# mult-mixer.net
KiCad netlist of a schematic drawn in EAGLE
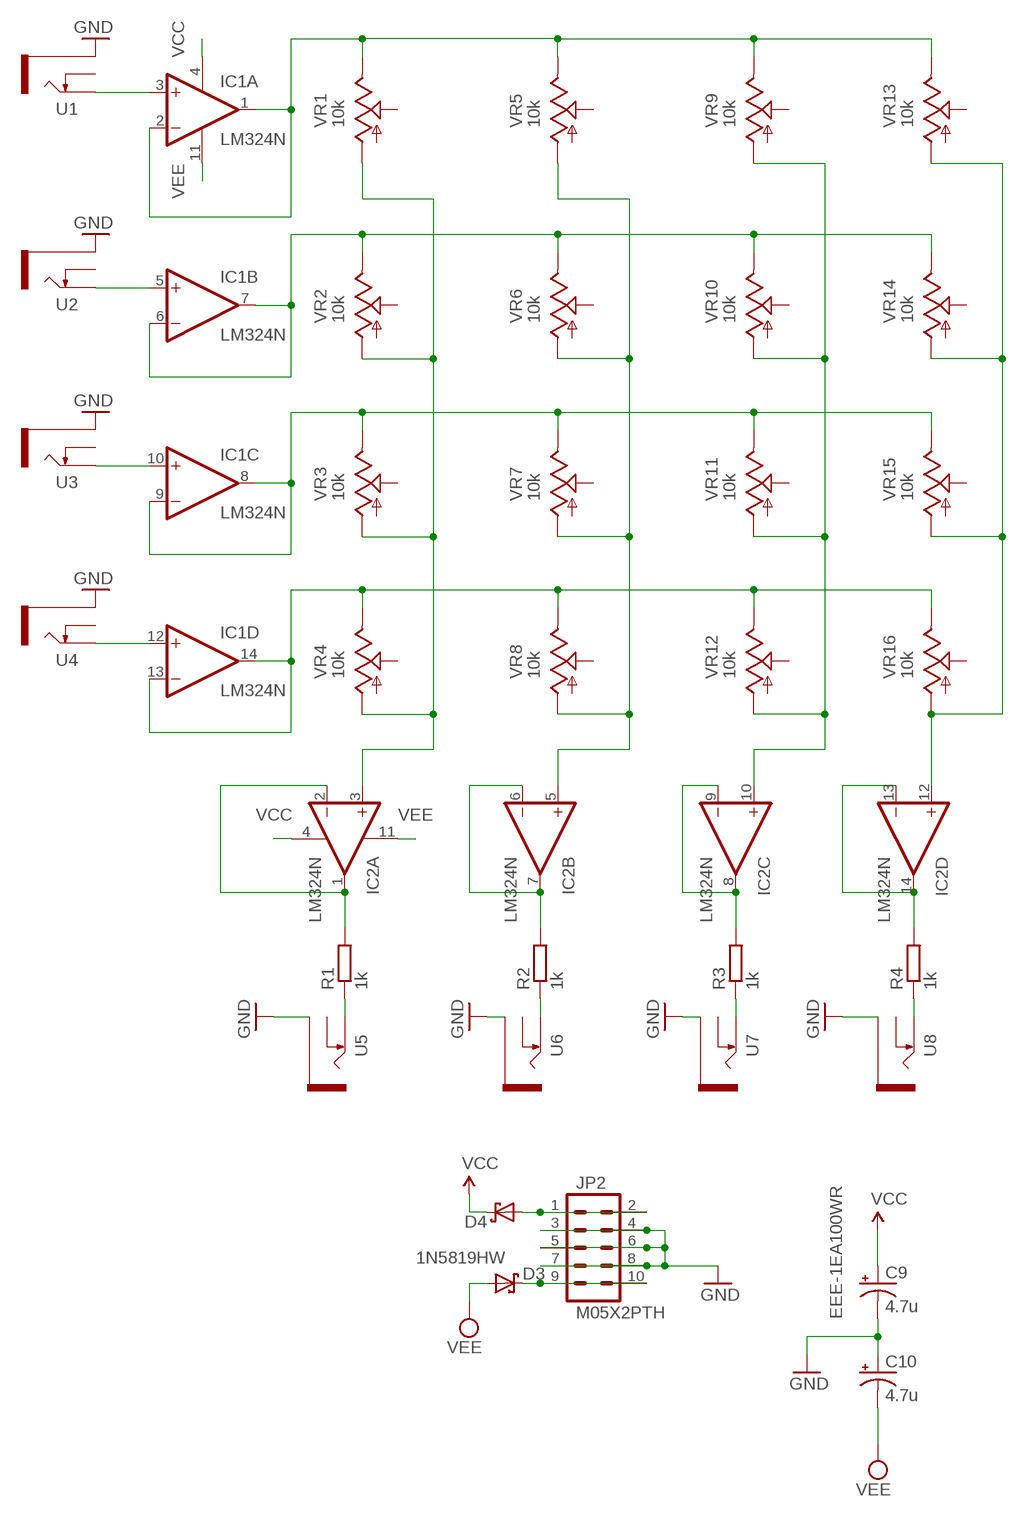
[diagram p0: schematic, sheet 1]

(export (version "E")
  (design (tool "Eeschema 10.0.6"))
  (components
    (comp (ref "C9")
      (value "4.7u")
      (footprint "eagle-import:PANASONIC_A")
      (libsource (lib "eagle-import") (part "CPOL-USA"))
    )
    (comp (ref "C10")
      (value "4.7u")
      (footprint "eagle-import:PANASONIC_A")
      (libsource (lib "eagle-import") (part "CPOL-USA"))
    )
    (comp (ref "D3")
      (value "1N5819HW")
      (footprint "eagle-import:DO41-7.6")
      (libsource (lib "eagle-import") (part "1N5819-B"))
    )
    (comp (ref "D4")
      (value "1N5819HW")
      (footprint "eagle-import:DO41-7.6")
      (libsource (lib "eagle-import") (part "1N5819-B"))
    )
    (comp (ref "IC1")
      (value "LM324N")
      (footprint "eagle-import:DIL14")
      (libsource (lib "eagle-import") (part "LM324N"))
    )
    (comp (ref "IC2")
      (value "LM324N")
      (footprint "eagle-import:DIL14")
      (libsource (lib "eagle-import") (part "LM324N"))
    )
    (comp (ref "JP2")
      (value "M05X2PTH")
      (footprint "eagle-import:AVR_ICSP")
      (libsource (lib "eagle-import") (part "M05X2PTH"))
    )
    (comp (ref "R1")
      (value "1k")
      (footprint "eagle-import:10MM_RESISTOR")
      (libsource (lib "eagle-import") (part "RESISTOR10MM_RESISTOR"))
    )
    (comp (ref "R2")
      (value "1k")
      (footprint "eagle-import:10MM_RESISTOR")
      (libsource (lib "eagle-import") (part "RESISTOR10MM_RESISTOR"))
    )
    (comp (ref "R3")
      (value "1k")
      (footprint "eagle-import:10MM_RESISTOR")
      (libsource (lib "eagle-import") (part "RESISTOR10MM_RESISTOR"))
    )
    (comp (ref "R4")
      (value "1k")
      (footprint "eagle-import:10MM_RESISTOR")
      (libsource (lib "eagle-import") (part "RESISTOR10MM_RESISTOR"))
    )
    (comp (ref "U1")
      (value "THONKICONNNEW")
      (footprint "eagle-import:WQP-PJ301M-12_JACK")
      (libsource (lib "eagle-import") (part "THONKICONNNEW"))
    )
    (comp (ref "U2")
      (value "THONKICONNNEW")
      (footprint "eagle-import:WQP-PJ301M-12_JACK")
      (libsource (lib "eagle-import") (part "THONKICONNNEW"))
    )
    (comp (ref "U3")
      (value "THONKICONNNEW")
      (footprint "eagle-import:WQP-PJ301M-12_JACK")
      (libsource (lib "eagle-import") (part "THONKICONNNEW"))
    )
    (comp (ref "U4")
      (value "THONKICONNNEW")
      (footprint "eagle-import:WQP-PJ301M-12_JACK")
      (libsource (lib "eagle-import") (part "THONKICONNNEW"))
    )
    (comp (ref "U5")
      (value "THONKICONNNEW")
      (footprint "eagle-import:WQP-PJ301M-12_JACK")
      (libsource (lib "eagle-import") (part "THONKICONNNEW"))
    )
    (comp (ref "U6")
      (value "THONKICONNNEW")
      (footprint "eagle-import:WQP-PJ301M-12_JACK")
      (libsource (lib "eagle-import") (part "THONKICONNNEW"))
    )
    (comp (ref "U7")
      (value "THONKICONNNEW")
      (footprint "eagle-import:WQP-PJ301M-12_JACK")
      (libsource (lib "eagle-import") (part "THONKICONNNEW"))
    )
    (comp (ref "U8")
      (value "THONKICONNNEW")
      (footprint "eagle-import:WQP-PJ301M-12_JACK")
      (libsource (lib "eagle-import") (part "THONKICONNNEW"))
    )
    (comp (ref "VR1")
      (value "10k")
      (footprint "eagle-import:9MM_SNAP-IN_POT")
      (libsource (lib "eagle-import") (part "9MM_SNAP-IN_POT_"))
    )
    (comp (ref "VR2")
      (value "10k")
      (footprint "eagle-import:9MM_SNAP-IN_POT")
      (libsource (lib "eagle-import") (part "9MM_SNAP-IN_POT_"))
    )
    (comp (ref "VR3")
      (value "10k")
      (footprint "eagle-import:9MM_SNAP-IN_POT")
      (libsource (lib "eagle-import") (part "9MM_SNAP-IN_POT_"))
    )
    (comp (ref "VR4")
      (value "10k")
      (footprint "eagle-import:9MM_SNAP-IN_POT")
      (libsource (lib "eagle-import") (part "9MM_SNAP-IN_POT_"))
    )
    (comp (ref "VR5")
      (value "10k")
      (footprint "eagle-import:9MM_SNAP-IN_POT")
      (libsource (lib "eagle-import") (part "9MM_SNAP-IN_POT_"))
    )
    (comp (ref "VR6")
      (value "10k")
      (footprint "eagle-import:9MM_SNAP-IN_POT")
      (libsource (lib "eagle-import") (part "9MM_SNAP-IN_POT_"))
    )
    (comp (ref "VR7")
      (value "10k")
      (footprint "eagle-import:9MM_SNAP-IN_POT")
      (libsource (lib "eagle-import") (part "9MM_SNAP-IN_POT_"))
    )
    (comp (ref "VR8")
      (value "10k")
      (footprint "eagle-import:9MM_SNAP-IN_POT")
      (libsource (lib "eagle-import") (part "9MM_SNAP-IN_POT_"))
    )
    (comp (ref "VR9")
      (value "10k")
      (footprint "eagle-import:9MM_SNAP-IN_POT")
      (libsource (lib "eagle-import") (part "9MM_SNAP-IN_POT_"))
    )
    (comp (ref "VR10")
      (value "10k")
      (footprint "eagle-import:9MM_SNAP-IN_POT")
      (libsource (lib "eagle-import") (part "9MM_SNAP-IN_POT_"))
    )
    (comp (ref "VR11")
      (value "10k")
      (footprint "eagle-import:9MM_SNAP-IN_POT")
      (libsource (lib "eagle-import") (part "9MM_SNAP-IN_POT_"))
    )
    (comp (ref "VR12")
      (value "10k")
      (footprint "eagle-import:9MM_SNAP-IN_POT")
      (libsource (lib "eagle-import") (part "9MM_SNAP-IN_POT_"))
    )
    (comp (ref "VR13")
      (value "10k")
      (footprint "eagle-import:9MM_SNAP-IN_POT")
      (libsource (lib "eagle-import") (part "9MM_SNAP-IN_POT_"))
    )
    (comp (ref "VR14")
      (value "10k")
      (footprint "eagle-import:9MM_SNAP-IN_POT")
      (libsource (lib "eagle-import") (part "9MM_SNAP-IN_POT_"))
    )
    (comp (ref "VR15")
      (value "10k")
      (footprint "eagle-import:9MM_SNAP-IN_POT")
      (libsource (lib "eagle-import") (part "9MM_SNAP-IN_POT_"))
    )
    (comp (ref "VR16")
      (value "10k")
      (footprint "eagle-import:9MM_SNAP-IN_POT")
      (libsource (lib "eagle-import") (part "9MM_SNAP-IN_POT_"))
    )
  )
  (nets
    (net (code "1") (name "GND") (class "Default")
      (node (ref "C10") (pin "+") (pinfunction "+_+") (pintype "passive"))
      (node (ref "C9") (pin "-") (pinfunction "-_-") (pintype "passive"))
      (node (ref "JP2") (pin "3") (pinfunction "3_3") (pintype "passive"))
      (node (ref "JP2") (pin "4") (pinfunction "4_4") (pintype "passive"))
      (node (ref "JP2") (pin "5") (pinfunction "5_5") (pintype "passive"))
      (node (ref "JP2") (pin "6") (pinfunction "6_6") (pintype "passive"))
      (node (ref "JP2") (pin "7") (pinfunction "7_7") (pintype "passive"))
      (node (ref "JP2") (pin "8") (pinfunction "8_8") (pintype "passive"))
      (node (ref "U1") (pin "P$3_SLEEVE") (pinfunction "SLEEVE_P$3_SLEEVE") (pintype "passive"))
      (node (ref "U2") (pin "P$3_SLEEVE") (pinfunction "SLEEVE_P$3_SLEEVE") (pintype "passive"))
      (node (ref "U3") (pin "P$3_SLEEVE") (pinfunction "SLEEVE_P$3_SLEEVE") (pintype "passive"))
      (node (ref "U4") (pin "P$3_SLEEVE") (pinfunction "SLEEVE_P$3_SLEEVE") (pintype "passive"))
      (node (ref "U5") (pin "P$3_SLEEVE") (pinfunction "SLEEVE_P$3_SLEEVE") (pintype "passive"))
      (node (ref "U6") (pin "P$3_SLEEVE") (pinfunction "SLEEVE_P$3_SLEEVE") (pintype "passive"))
      (node (ref "U7") (pin "P$3_SLEEVE") (pinfunction "SLEEVE_P$3_SLEEVE") (pintype "passive"))
      (node (ref "U8") (pin "P$3_SLEEVE") (pinfunction "SLEEVE_P$3_SLEEVE") (pintype "passive"))
    )
    (net (code "2") (name "Net-(D3-PadC)") (class "Default")
      (node (ref "D3") (pin "C") (pinfunction "C_C") (pintype "passive"))
      (node (ref "JP2") (pin "10") (pinfunction "10_10") (pintype "passive"))
      (node (ref "JP2") (pin "9") (pinfunction "9_9") (pintype "passive"))
    )
    (net (code "3") (name "Net-(D4-PadA)") (class "Default")
      (node (ref "D4") (pin "A") (pinfunction "A_A") (pintype "passive"))
      (node (ref "JP2") (pin "1") (pinfunction "1_1") (pintype "passive"))
      (node (ref "JP2") (pin "2") (pinfunction "2_2") (pintype "passive"))
    )
    (net (code "4") (name "Net-(IC1A-+IN)") (class "Default")
      (node (ref "IC1") (pin "3") (pinfunction "+IN_3") (pintype "input"))
      (node (ref "U1") (pin "P$1_TIP") (pinfunction "TIP_P$1_TIP") (pintype "passive"))
    )
    (net (code "5") (name "Net-(IC1A--IN)") (class "Default")
      (node (ref "IC1") (pin "1") (pinfunction "OUT_1") (pintype "output"))
      (node (ref "IC1") (pin "2") (pinfunction "-IN_2") (pintype "input"))
      (node (ref "VR1") (pin "3") (pinfunction "E_3") (pintype "passive"))
      (node (ref "VR13") (pin "3") (pinfunction "E_3") (pintype "passive"))
      (node (ref "VR5") (pin "3") (pinfunction "E_3") (pintype "passive"))
      (node (ref "VR9") (pin "3") (pinfunction "E_3") (pintype "passive"))
    )
    (net (code "6") (name "Net-(IC1B-+IN)") (class "Default")
      (node (ref "IC1") (pin "5") (pinfunction "+IN_5") (pintype "input"))
      (node (ref "U2") (pin "P$1_TIP") (pinfunction "TIP_P$1_TIP") (pintype "passive"))
    )
    (net (code "7") (name "Net-(IC1B--IN)") (class "Default")
      (node (ref "IC1") (pin "6") (pinfunction "-IN_6") (pintype "input"))
      (node (ref "IC1") (pin "7") (pinfunction "OUT_7") (pintype "output"))
      (node (ref "VR10") (pin "3") (pinfunction "E_3") (pintype "passive"))
      (node (ref "VR14") (pin "3") (pinfunction "E_3") (pintype "passive"))
      (node (ref "VR2") (pin "3") (pinfunction "E_3") (pintype "passive"))
      (node (ref "VR6") (pin "3") (pinfunction "E_3") (pintype "passive"))
    )
    (net (code "8") (name "Net-(IC1C-+IN)") (class "Default")
      (node (ref "IC1") (pin "10") (pinfunction "+IN_10") (pintype "input"))
      (node (ref "U3") (pin "P$1_TIP") (pinfunction "TIP_P$1_TIP") (pintype "passive"))
    )
    (net (code "9") (name "Net-(IC1C--IN)") (class "Default")
      (node (ref "IC1") (pin "8") (pinfunction "OUT_8") (pintype "output"))
      (node (ref "IC1") (pin "9") (pinfunction "-IN_9") (pintype "input"))
      (node (ref "VR11") (pin "3") (pinfunction "E_3") (pintype "passive"))
      (node (ref "VR15") (pin "3") (pinfunction "E_3") (pintype "passive"))
      (node (ref "VR3") (pin "3") (pinfunction "E_3") (pintype "passive"))
      (node (ref "VR7") (pin "3") (pinfunction "E_3") (pintype "passive"))
    )
    (net (code "10") (name "Net-(IC1D-+IN)") (class "Default")
      (node (ref "IC1") (pin "12") (pinfunction "+IN_12") (pintype "input"))
      (node (ref "U4") (pin "P$1_TIP") (pinfunction "TIP_P$1_TIP") (pintype "passive"))
    )
    (net (code "11") (name "Net-(IC1D--IN)") (class "Default")
      (node (ref "IC1") (pin "13") (pinfunction "-IN_13") (pintype "input"))
      (node (ref "IC1") (pin "14") (pinfunction "OUT_14") (pintype "output"))
      (node (ref "VR12") (pin "3") (pinfunction "E_3") (pintype "passive"))
      (node (ref "VR16") (pin "3") (pinfunction "E_3") (pintype "passive"))
      (node (ref "VR4") (pin "3") (pinfunction "E_3") (pintype "passive"))
      (node (ref "VR8") (pin "3") (pinfunction "E_3") (pintype "passive"))
    )
    (net (code "12") (name "Net-(IC2A-+IN)") (class "Default")
      (node (ref "IC2") (pin "3") (pinfunction "+IN_3") (pintype "input"))
      (node (ref "VR1") (pin "1") (pinfunction "A_1") (pintype "passive"))
      (node (ref "VR2") (pin "1") (pinfunction "A_1") (pintype "passive"))
      (node (ref "VR3") (pin "1") (pinfunction "A_1") (pintype "passive"))
      (node (ref "VR4") (pin "1") (pinfunction "A_1") (pintype "passive"))
    )
    (net (code "13") (name "Net-(IC2A--IN)") (class "Default")
      (node (ref "IC2") (pin "1") (pinfunction "OUT_1") (pintype "output"))
      (node (ref "IC2") (pin "2") (pinfunction "-IN_2") (pintype "input"))
      (node (ref "R1") (pin "2") (pinfunction "2_2") (pintype "passive"))
    )
    (net (code "14") (name "Net-(IC2B-+IN)") (class "Default")
      (node (ref "IC2") (pin "5") (pinfunction "+IN_5") (pintype "input"))
      (node (ref "VR5") (pin "1") (pinfunction "A_1") (pintype "passive"))
      (node (ref "VR6") (pin "1") (pinfunction "A_1") (pintype "passive"))
      (node (ref "VR7") (pin "1") (pinfunction "A_1") (pintype "passive"))
      (node (ref "VR8") (pin "1") (pinfunction "A_1") (pintype "passive"))
    )
    (net (code "15") (name "Net-(IC2B--IN)") (class "Default")
      (node (ref "IC2") (pin "6") (pinfunction "-IN_6") (pintype "input"))
      (node (ref "IC2") (pin "7") (pinfunction "OUT_7") (pintype "output"))
      (node (ref "R2") (pin "2") (pinfunction "2_2") (pintype "passive"))
    )
    (net (code "16") (name "Net-(IC2C-+IN)") (class "Default")
      (node (ref "IC2") (pin "10") (pinfunction "+IN_10") (pintype "input"))
      (node (ref "VR10") (pin "1") (pinfunction "A_1") (pintype "passive"))
      (node (ref "VR11") (pin "1") (pinfunction "A_1") (pintype "passive"))
      (node (ref "VR12") (pin "1") (pinfunction "A_1") (pintype "passive"))
      (node (ref "VR9") (pin "1") (pinfunction "A_1") (pintype "passive"))
    )
    (net (code "17") (name "Net-(IC2C--IN)") (class "Default")
      (node (ref "IC2") (pin "8") (pinfunction "OUT_8") (pintype "output"))
      (node (ref "IC2") (pin "9") (pinfunction "-IN_9") (pintype "input"))
      (node (ref "R3") (pin "2") (pinfunction "2_2") (pintype "passive"))
    )
    (net (code "18") (name "Net-(IC2D-+IN)") (class "Default")
      (node (ref "IC2") (pin "12") (pinfunction "+IN_12") (pintype "input"))
      (node (ref "VR13") (pin "1") (pinfunction "A_1") (pintype "passive"))
      (node (ref "VR14") (pin "1") (pinfunction "A_1") (pintype "passive"))
      (node (ref "VR15") (pin "1") (pinfunction "A_1") (pintype "passive"))
      (node (ref "VR16") (pin "1") (pinfunction "A_1") (pintype "passive"))
    )
    (net (code "19") (name "Net-(IC2D--IN)") (class "Default")
      (node (ref "IC2") (pin "13") (pinfunction "-IN_13") (pintype "input"))
      (node (ref "IC2") (pin "14") (pinfunction "OUT_14") (pintype "output"))
      (node (ref "R4") (pin "2") (pinfunction "2_2") (pintype "passive"))
    )
    (net (code "20") (name "Net-(U5-TIP)") (class "Default")
      (node (ref "R1") (pin "1") (pinfunction "1_1") (pintype "passive"))
      (node (ref "U5") (pin "P$1_TIP") (pinfunction "TIP_P$1_TIP") (pintype "passive"))
    )
    (net (code "21") (name "Net-(U6-TIP)") (class "Default")
      (node (ref "R2") (pin "1") (pinfunction "1_1") (pintype "passive"))
      (node (ref "U6") (pin "P$1_TIP") (pinfunction "TIP_P$1_TIP") (pintype "passive"))
    )
    (net (code "22") (name "Net-(U7-TIP)") (class "Default")
      (node (ref "R3") (pin "1") (pinfunction "1_1") (pintype "passive"))
      (node (ref "U7") (pin "P$1_TIP") (pinfunction "TIP_P$1_TIP") (pintype "passive"))
    )
    (net (code "23") (name "Net-(U8-TIP)") (class "Default")
      (node (ref "R4") (pin "1") (pinfunction "1_1") (pintype "passive"))
      (node (ref "U8") (pin "P$1_TIP") (pinfunction "TIP_P$1_TIP") (pintype "passive"))
    )
    (net (code "24") (name "VCC") (class "Default")
      (node (ref "C9") (pin "+") (pinfunction "+_+") (pintype "passive"))
      (node (ref "D4") (pin "C") (pinfunction "C_C") (pintype "passive"))
      (node (ref "IC1") (pin "4") (pinfunction "V+_4") (pintype "power_in"))
      (node (ref "IC2") (pin "4") (pinfunction "V+_4") (pintype "power_in"))
    )
    (net (code "25") (name "VEE") (class "Default")
      (node (ref "C10") (pin "-") (pinfunction "-_-") (pintype "passive"))
      (node (ref "D3") (pin "A") (pinfunction "A_A") (pintype "passive"))
      (node (ref "IC1") (pin "11") (pinfunction "V-_11") (pintype "power_in"))
      (node (ref "IC2") (pin "11") (pinfunction "V-_11") (pintype "power_in"))
    )
    (net (code "26") (name "unconnected-(U1-SWITCH-PadP$2_SWITCH)") (class "Default")
      (node (ref "U1") (pin "P$2_SWITCH") (pinfunction "SWITCH_P$2_SWITCH") (pintype "passive"))
    )
    (net (code "27") (name "unconnected-(U2-SWITCH-PadP$2_SWITCH)") (class "Default")
      (node (ref "U2") (pin "P$2_SWITCH") (pinfunction "SWITCH_P$2_SWITCH") (pintype "passive"))
    )
    (net (code "28") (name "unconnected-(U3-SWITCH-PadP$2_SWITCH)") (class "Default")
      (node (ref "U3") (pin "P$2_SWITCH") (pinfunction "SWITCH_P$2_SWITCH") (pintype "passive"))
    )
    (net (code "29") (name "unconnected-(U4-SWITCH-PadP$2_SWITCH)") (class "Default")
      (node (ref "U4") (pin "P$2_SWITCH") (pinfunction "SWITCH_P$2_SWITCH") (pintype "passive"))
    )
    (net (code "30") (name "unconnected-(U5-SWITCH-PadP$2_SWITCH)") (class "Default")
      (node (ref "U5") (pin "P$2_SWITCH") (pinfunction "SWITCH_P$2_SWITCH") (pintype "passive"))
    )
    (net (code "31") (name "unconnected-(U6-SWITCH-PadP$2_SWITCH)") (class "Default")
      (node (ref "U6") (pin "P$2_SWITCH") (pinfunction "SWITCH_P$2_SWITCH") (pintype "passive"))
    )
    (net (code "32") (name "unconnected-(U7-SWITCH-PadP$2_SWITCH)") (class "Default")
      (node (ref "U7") (pin "P$2_SWITCH") (pinfunction "SWITCH_P$2_SWITCH") (pintype "passive"))
    )
    (net (code "33") (name "unconnected-(U8-SWITCH-PadP$2_SWITCH)") (class "Default")
      (node (ref "U8") (pin "P$2_SWITCH") (pinfunction "SWITCH_P$2_SWITCH") (pintype "passive"))
    )
    (net (code "34") (name "unconnected-(VR1-S-Pad2)") (class "Default")
      (node (ref "VR1") (pin "2") (pinfunction "S_2") (pintype "passive"))
    )
    (net (code "35") (name "unconnected-(VR2-S-Pad2)") (class "Default")
      (node (ref "VR2") (pin "2") (pinfunction "S_2") (pintype "passive"))
    )
    (net (code "36") (name "unconnected-(VR3-S-Pad2)") (class "Default")
      (node (ref "VR3") (pin "2") (pinfunction "S_2") (pintype "passive"))
    )
    (net (code "37") (name "unconnected-(VR4-S-Pad2)") (class "Default")
      (node (ref "VR4") (pin "2") (pinfunction "S_2") (pintype "passive"))
    )
    (net (code "38") (name "unconnected-(VR5-S-Pad2)") (class "Default")
      (node (ref "VR5") (pin "2") (pinfunction "S_2") (pintype "passive"))
    )
    (net (code "39") (name "unconnected-(VR6-S-Pad2)") (class "Default")
      (node (ref "VR6") (pin "2") (pinfunction "S_2") (pintype "passive"))
    )
    (net (code "40") (name "unconnected-(VR7-S-Pad2)") (class "Default")
      (node (ref "VR7") (pin "2") (pinfunction "S_2") (pintype "passive"))
    )
    (net (code "41") (name "unconnected-(VR8-S-Pad2)") (class "Default")
      (node (ref "VR8") (pin "2") (pinfunction "S_2") (pintype "passive"))
    )
    (net (code "42") (name "unconnected-(VR9-S-Pad2)") (class "Default")
      (node (ref "VR9") (pin "2") (pinfunction "S_2") (pintype "passive"))
    )
    (net (code "43") (name "unconnected-(VR10-S-Pad2)") (class "Default")
      (node (ref "VR10") (pin "2") (pinfunction "S_2") (pintype "passive"))
    )
    (net (code "44") (name "unconnected-(VR11-S-Pad2)") (class "Default")
      (node (ref "VR11") (pin "2") (pinfunction "S_2") (pintype "passive"))
    )
    (net (code "45") (name "unconnected-(VR12-S-Pad2)") (class "Default")
      (node (ref "VR12") (pin "2") (pinfunction "S_2") (pintype "passive"))
    )
    (net (code "46") (name "unconnected-(VR13-S-Pad2)") (class "Default")
      (node (ref "VR13") (pin "2") (pinfunction "S_2") (pintype "passive"))
    )
    (net (code "47") (name "unconnected-(VR14-S-Pad2)") (class "Default")
      (node (ref "VR14") (pin "2") (pinfunction "S_2") (pintype "passive"))
    )
    (net (code "48") (name "unconnected-(VR15-S-Pad2)") (class "Default")
      (node (ref "VR15") (pin "2") (pinfunction "S_2") (pintype "passive"))
    )
    (net (code "49") (name "unconnected-(VR16-S-Pad2)") (class "Default")
      (node (ref "VR16") (pin "2") (pinfunction "S_2") (pintype "passive"))
    )
  )
)
